# io.net
KiCad netlist of a schematic drawn in Altium Designer
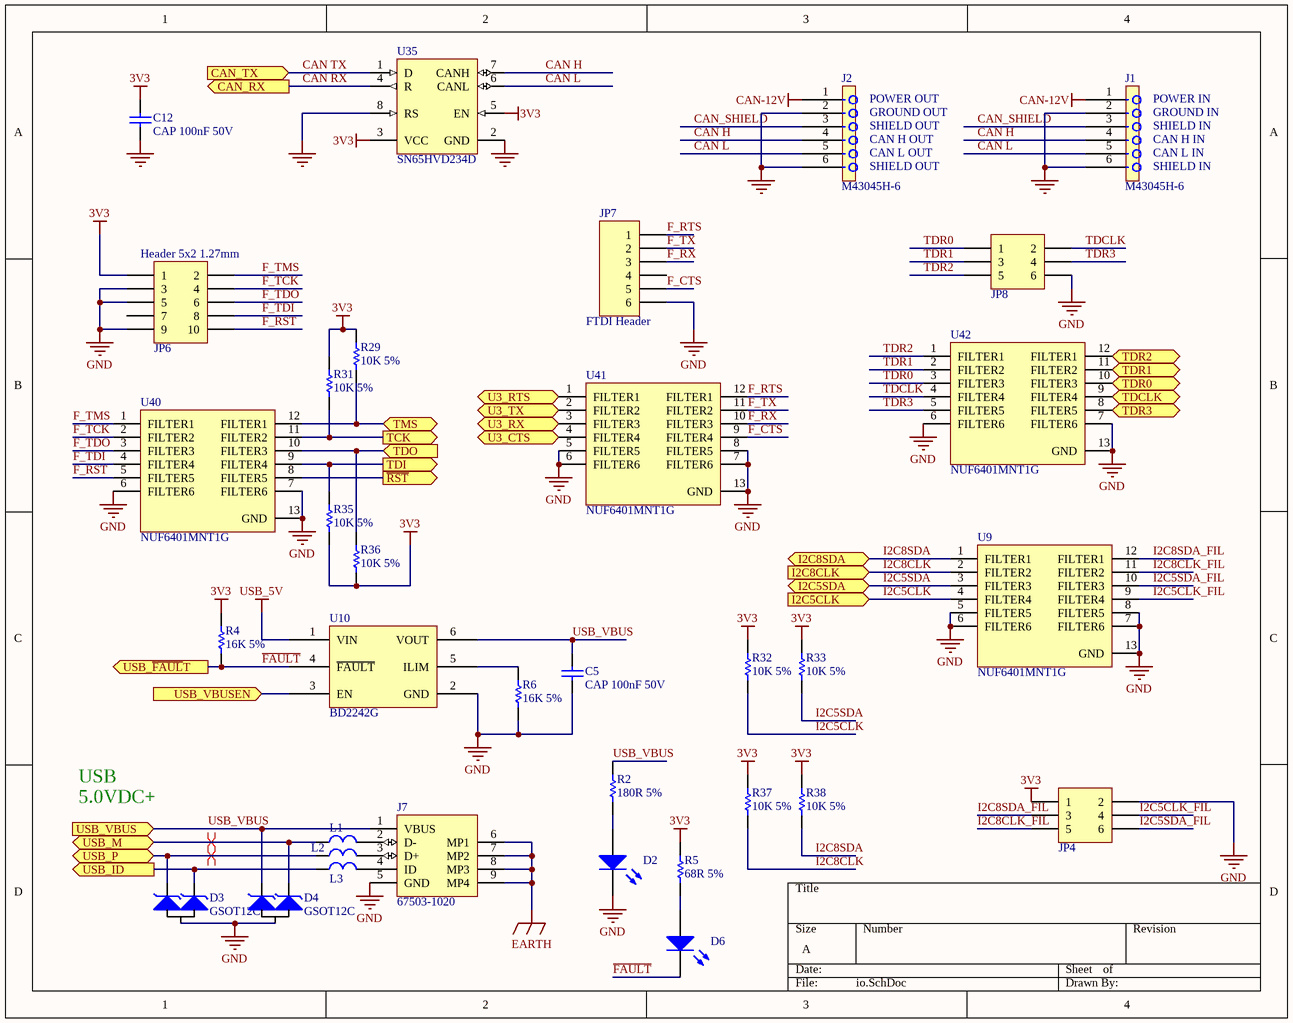
[diagram p0: io.SchDoc]

(export (version "E")
  (design (tool "Eeschema 10.0.6"))
  (components
    (comp (ref "C5")
      (value "CAP 100nF 50V")
      (footprint "CAPC0603(1608)100_M")
      (description "CAP 100nF 50V Â±0.1pF 0603 (1608 Metric) Thickness 1mm SMD")
      (fields (field (name "TOLERANCE") "Â±0.1pF"))
      (libsource (lib "Altium Content Vault") (part "CMP-1035-00010-1"))
    )
    (comp (ref "C12")
      (value "CAP 100nF 50V")
      (footprint "CAPC0603(1608)100_M")
      (description "CAP 100nF 50V Â±0.1pF 0603 (1608 Metric) Thickness 1mm SMD")
      (fields (field (name "TOLERANCE") "Â±0.1pF"))
      (libsource (lib "Altium Content Vault") (part "CMP-1035-00010-1"))
    )
    (comp (ref "D2")
      (value "LED")
      (footprint "LED-0603")
      (description "Typical RED, GREEN, YELLOW, AMBER GaAs LED")
      (fields (field (name "PUBLISHER") "Altium Limited"))
      (libsource (lib "HSBNE-Vend") (part "LED"))
    )
    (comp (ref "D3")
      (value "GSOT12C")
      (footprint "SOT-23 - ESD")
      (description "DIO GSOT12C ESD 2LINE 12V SOT23")
      (fields (field (name "MPN") "GSOT12C-E3-08"))
      (libsource (lib "HSBNE-Vend") (part "2749"))
    )
    (comp (ref "D4")
      (value "GSOT12C")
      (footprint "SOT-23 - ESD")
      (description "DIO GSOT12C ESD 2LINE 12V SOT23")
      (fields (field (name "MPN") "GSOT12C-E3-08"))
      (libsource (lib "HSBNE-Vend") (part "2749"))
    )
    (comp (ref "D6")
      (value "LED")
      (footprint "LED-0603")
      (description "Typical RED, GREEN, YELLOW, AMBER GaAs LED")
      (fields (field (name "PUBLISHER") "Altium Limited"))
      (libsource (lib "HSBNE-Vend") (part "LED"))
    )
    (comp (ref "J1") (value "M43045H-6") (footprint "M43045H-6") (libsource (lib "HSBNE-Vend") (part "CON6")))
    (comp (ref "J2") (value "M43045H-6") (footprint "M43045H-6") (libsource (lib "HSBNE-Vend") (part "CON6")))
    (comp (ref "J7")
      (value "67503-1020")
      (footprint "MOLX-67503-1020_V")
      (description "USB, MINI, SMD, RA KME04-USBMU03A01")
      (fields (field (name "MANUFACTURER") "Molex"))
      (libsource (lib "Altium Content Vault") (part "MOLX-67503-1020"))
    )
    (comp (ref "JP4")
      (value "Header 3x2 2.54mm")
      (footprint "2X3")
      (description "Header, 6-Pin")
      (libsource (lib "HSBNE-Vend") (part "Header 3x2"))
    )
    (comp (ref "JP6")
      (value "Header 5x2 1.27mm")
      (footprint "SOP10")
      (description "Program")
      (libsource (lib "HSBNE-Vend") (part "Header 5x2"))
    )
    (comp (ref "JP7")
      (value "FTDI Header")
      (footprint "1X6")
      (description "Header, 6-Pin")
      (libsource (lib "snarc+3") (part "Header 6"))
    )
    (comp (ref "JP8")
      (value "Header 3x2 2.54mm")
      (footprint "2X3")
      (description "Header, 6-Pin")
      (libsource (lib "HSBNE-Vend") (part "Header 3x2"))
    )
    (comp (ref "L1")
      (value "MPZ1608S102A")
      (footprint "0603")
      (description "IND FERRITE CHIP BEAD 1000 OHM @ 100MHz 800mA 0603")
      (libsource (lib "LXPN") (part "2982"))
    )
    (comp (ref "L2")
      (value "MPZ1608S102A")
      (footprint "0603")
      (description "IND FERRITE CHIP BEAD 1000 OHM @ 100MHz 800mA 0603")
      (libsource (lib "LXPN") (part "2982"))
    )
    (comp (ref "L3")
      (value "MPZ1608S102A")
      (footprint "0603")
      (description "IND FERRITE CHIP BEAD 1000 OHM @ 100MHz 800mA 0603")
      (libsource (lib "LXPN") (part "2982"))
    )
    (comp (ref "R2")
      (value "180R 5%")
      (footprint "RESC0603(1608)_L")
      (description "180R 0.1W 5% 0603 (1608 Metric)  SMD")
      (fields (field (name "POWER") "0.1 W") (field (name "TOLERANCE") "5 %"))
      (libsource (lib "Altium Content Vault") (part "CMP-1012-00056-1"))
    )
    (comp (ref "R4")
      (value "16K 5%")
      (footprint "RESC0603(1608)_L")
      (description "16K 0.1W 5% 0603 (1608 Metric)  SMD")
      (fields (field (name "TOLERANCE") "5 %") (field (name "POWER") "0.1 W"))
      (libsource (lib "Altium Content Vault") (part "RES"))
    )
    (comp (ref "R5")
      (value "68R 5%")
      (footprint "RESC0603(1608)_M")
      (description "68R 0.1W 5% 0603 (1608 Metric)  SMD")
      (fields (field (name "POWER") "0.1 W") (field (name "TOLERANCE") "5 %"))
      (libsource (lib "Altium Content Vault") (part "CMP-1012-00046-1"))
    )
    (comp (ref "R6")
      (value "16K 5%")
      (footprint "RESC0603(1608)_L")
      (description "16K 0.1W 5% 0603 (1608 Metric)  SMD")
      (fields (field (name "TOLERANCE") "5 %") (field (name "POWER") "0.1 W"))
      (libsource (lib "Altium Content Vault") (part "RES"))
    )
    (comp (ref "R29")
      (value "10K 5%")
      (footprint "RESC0603(1608)_N")
      (description "10K 0.1W 5% 0603 (1608 Metric)  SMD")
      (fields (field (name "TOLERANCE") "5 %") (field (name "POWER") "0.1 W"))
      (libsource (lib "Altium Content Vault") (part "RES"))
    )
    (comp (ref "R31")
      (value "10K 5%")
      (footprint "RESC0603(1608)_N")
      (description "10K 0.1W 5% 0603 (1608 Metric)  SMD")
      (fields (field (name "TOLERANCE") "5 %") (field (name "POWER") "0.1 W"))
      (libsource (lib "Altium Content Vault") (part "RES"))
    )
    (comp (ref "R32")
      (value "10K 5%")
      (footprint "RESC0603(1608)_N")
      (description "10K 0.1W 5% 0603 (1608 Metric)  SMD")
      (fields (field (name "TOLERANCE") "5 %") (field (name "POWER") "0.1 W"))
      (libsource (lib "Altium Content Vault") (part "RES"))
    )
    (comp (ref "R33")
      (value "10K 5%")
      (footprint "RESC0603(1608)_N")
      (description "10K 0.1W 5% 0603 (1608 Metric)  SMD")
      (fields (field (name "TOLERANCE") "5 %") (field (name "POWER") "0.1 W"))
      (libsource (lib "Altium Content Vault") (part "RES"))
    )
    (comp (ref "R35")
      (value "10K 5%")
      (footprint "RESC0603(1608)_N")
      (description "10K 0.1W 5% 0603 (1608 Metric)  SMD")
      (fields (field (name "TOLERANCE") "5 %") (field (name "POWER") "0.1 W"))
      (libsource (lib "Altium Content Vault") (part "RES"))
    )
    (comp (ref "R36")
      (value "10K 5%")
      (footprint "RESC0603(1608)_N")
      (description "10K 0.1W 5% 0603 (1608 Metric)  SMD")
      (fields (field (name "TOLERANCE") "5 %") (field (name "POWER") "0.1 W"))
      (libsource (lib "Altium Content Vault") (part "RES"))
    )
    (comp (ref "R37")
      (value "10K 5%")
      (footprint "RESC0603(1608)_N")
      (description "10K 0.1W 5% 0603 (1608 Metric)  SMD")
      (fields (field (name "TOLERANCE") "5 %") (field (name "POWER") "0.1 W"))
      (libsource (lib "Altium Content Vault") (part "RES"))
    )
    (comp (ref "R38")
      (value "10K 5%")
      (footprint "RESC0603(1608)_N")
      (description "10K 0.1W 5% 0603 (1608 Metric)  SMD")
      (fields (field (name "TOLERANCE") "5 %") (field (name "POWER") "0.1 W"))
      (libsource (lib "Altium Content Vault") (part "RES"))
    )
    (comp (ref "U9")
      (value "NUF6401MNT1G")
      (footprint "ONSC-DFN-12-506AD-01_V")
      (fields (field (name "MANUFACTURER") "On Semiconductor"))
      (libsource (lib "Altium Content Vault") (part "CMP-1066-00005-1"))
    )
    (comp (ref "U10")
      (value "BD2242G")
      (footprint "SOT23-6")
      (description "BD2242G-GTR")
      (libsource (lib "HSBNE-Vend") (part "RT9728A"))
    )
    (comp (ref "U35")
      (value "SN65HVD234D")
      (footprint "D8_M")
      (fields (field (name "MANUFACTURER") "Texas Instruments"))
      (libsource (lib "Altium Content Vault") (part "TI-SN65HVD234-SOIC_D-8"))
    )
    (comp (ref "U40")
      (value "NUF6401MNT1G")
      (footprint "ONSC-DFN-12-506AD-01_V")
      (fields (field (name "MANUFACTURER") "On Semiconductor"))
      (libsource (lib "HSBNE-Vend") (part "CMP-1066-00005-1"))
    )
    (comp (ref "U41")
      (value "NUF6401MNT1G")
      (footprint "ONSC-DFN-12-506AD-01_V")
      (fields (field (name "MANUFACTURER") "On Semiconductor"))
      (libsource (lib "HSBNE-Vend") (part "CMP-1066-00005-1"))
    )
    (comp (ref "U42")
      (value "NUF6401MNT1G")
      (footprint "ONSC-DFN-12-506AD-01_V")
      (fields (field (name "MANUFACTURER") "On Semiconductor"))
      (libsource (lib "HSBNE-Vend") (part "CMP-1066-00005-1"))
    )
  )
  (nets
    (net (code "1") (name "/CAN H") (class "Default")
      (node (ref "J1") (pin "4") (pintype "passive"))
      (node (ref "J2") (pin "4") (pintype "passive"))
      (node (ref "U35") (pin "7") (pinfunction "CANH_7") (pintype "bidirectional"))
    )
    (net (code "2") (name "/CAN L") (class "Default")
      (node (ref "J1") (pin "5") (pintype "passive"))
      (node (ref "J2") (pin "5") (pintype "passive"))
      (node (ref "U35") (pin "6") (pinfunction "CANL_6") (pintype "bidirectional"))
    )
    (net (code "3") (name "/CAN RX") (class "Default")
      (node (ref "U35") (pin "4") (pinfunction "R_4") (pintype "output"))
    )
    (net (code "4") (name "/CAN TX") (class "Default")
      (node (ref "U35") (pin "1") (pinfunction "D_1") (pintype "input"))
    )
    (net (code "5") (name "/CAN_SHIELD") (class "Default")
      (node (ref "J1") (pin "3") (pintype "passive"))
      (node (ref "J2") (pin "3") (pintype "passive"))
    )
    (net (code "6") (name "/F_CTS") (class "Default")
      (node (ref "JP7") (pin "5") (pinfunction "5_5") (pintype "passive"))
      (node (ref "U41") (pin "9") (pinfunction "FILTER4_9") (pintype "passive"))
    )
    (net (code "7") (name "/F_RTS") (class "Default")
      (node (ref "JP7") (pin "1") (pinfunction "1_1") (pintype "passive"))
      (node (ref "U41") (pin "12") (pinfunction "FILTER1_12") (pintype "passive"))
    )
    (net (code "8") (name "/F_RX") (class "Default")
      (node (ref "JP7") (pin "3") (pinfunction "3_3") (pintype "passive"))
      (node (ref "U41") (pin "10") (pinfunction "FILTER3_10") (pintype "passive"))
    )
    (net (code "9") (name "/F_TCK") (class "Default")
      (node (ref "JP6") (pin "4") (pinfunction "4_4") (pintype "passive"))
      (node (ref "U40") (pin "2") (pinfunction "FILTER2_2") (pintype "passive"))
    )
    (net (code "10") (name "/F_TDI") (class "Default")
      (node (ref "JP6") (pin "8") (pinfunction "8_8") (pintype "passive"))
      (node (ref "U40") (pin "4") (pinfunction "FILTER4_4") (pintype "passive"))
    )
    (net (code "11") (name "/F_TDO") (class "Default")
      (node (ref "JP6") (pin "6") (pinfunction "6_6") (pintype "passive"))
      (node (ref "U40") (pin "3") (pinfunction "FILTER3_3") (pintype "passive"))
    )
    (net (code "12") (name "/F_TMS") (class "Default")
      (node (ref "JP6") (pin "2") (pinfunction "2_2") (pintype "passive"))
      (node (ref "U40") (pin "1") (pinfunction "FILTER1_1") (pintype "passive"))
    )
    (net (code "13") (name "/F_TX") (class "Default")
      (node (ref "JP7") (pin "2") (pinfunction "2_2") (pintype "passive"))
      (node (ref "U41") (pin "11") (pinfunction "FILTER2_11") (pintype "passive"))
    )
    (net (code "14") (name "/F_~{RST}") (class "Default")
      (node (ref "JP6") (pin "10") (pinfunction "10_10") (pintype "passive"))
      (node (ref "U40") (pin "5") (pinfunction "FILTER5_5") (pintype "passive"))
    )
    (net (code "15") (name "/I2C5CLK") (class "Default")
      (node (ref "R32") (pin "1") (pinfunction "1_1") (pintype "passive"))
      (node (ref "U9") (pin "4") (pinfunction "FILTER4_4") (pintype "passive"))
    )
    (net (code "16") (name "/I2C5CLK_FIL") (class "Default")
      (node (ref "JP4") (pin "4") (pinfunction "4_4") (pintype "passive"))
      (node (ref "U9") (pin "9") (pinfunction "FILTER4_9") (pintype "passive"))
    )
    (net (code "17") (name "/I2C5SDA") (class "Default")
      (node (ref "R33") (pin "1") (pinfunction "1_1") (pintype "passive"))
      (node (ref "U9") (pin "3") (pinfunction "FILTER3_3") (pintype "passive"))
    )
    (net (code "18") (name "/I2C5SDA_FIL") (class "Default")
      (node (ref "JP4") (pin "6") (pinfunction "6_6") (pintype "passive"))
      (node (ref "U9") (pin "10") (pinfunction "FILTER3_10") (pintype "passive"))
    )
    (net (code "19") (name "/I2C8CLK") (class "Default")
      (node (ref "R37") (pin "1") (pinfunction "1_1") (pintype "passive"))
      (node (ref "U9") (pin "2") (pinfunction "FILTER2_2") (pintype "passive"))
    )
    (net (code "20") (name "/I2C8CLK_FIL") (class "Default")
      (node (ref "JP4") (pin "5") (pinfunction "5_5") (pintype "passive"))
      (node (ref "U9") (pin "11") (pinfunction "FILTER2_11") (pintype "passive"))
    )
    (net (code "21") (name "/I2C8SDA") (class "Default")
      (node (ref "R38") (pin "1") (pinfunction "1_1") (pintype "passive"))
      (node (ref "U9") (pin "1") (pinfunction "FILTER1_1") (pintype "passive"))
    )
    (net (code "22") (name "/I2C8SDA_FIL") (class "Default")
      (node (ref "JP4") (pin "3") (pinfunction "3_3") (pintype "passive"))
      (node (ref "U9") (pin "12") (pinfunction "FILTER1_12") (pintype "passive"))
    )
    (net (code "23") (name "/TCK") (class "Default")
      (node (ref "R31") (pin "1") (pinfunction "1_1") (pintype "passive"))
      (node (ref "U40") (pin "11") (pinfunction "FILTER2_11") (pintype "passive"))
    )
    (net (code "24") (name "/TDCLK") (class "Default")
      (node (ref "JP8") (pin "2") (pinfunction "2_2") (pintype "passive"))
      (node (ref "U42") (pin "4") (pinfunction "FILTER4_4") (pintype "passive"))
    )
    (net (code "25") (name "/TDI") (class "Default")
      (node (ref "R35") (pin "2") (pinfunction "2_2") (pintype "passive"))
      (node (ref "U40") (pin "9") (pinfunction "FILTER4_9") (pintype "passive"))
    )
    (net (code "26") (name "/TDO") (class "Default")
      (node (ref "R36") (pin "2") (pinfunction "2_2") (pintype "passive"))
      (node (ref "U40") (pin "10") (pinfunction "FILTER3_10") (pintype "passive"))
    )
    (net (code "27") (name "/TDR0") (class "Default")
      (node (ref "JP8") (pin "1") (pinfunction "1_1") (pintype "passive"))
      (node (ref "U42") (pin "3") (pinfunction "FILTER3_3") (pintype "passive"))
    )
    (net (code "28") (name "/TDR1") (class "Default")
      (node (ref "JP8") (pin "3") (pinfunction "3_3") (pintype "passive"))
      (node (ref "U42") (pin "2") (pinfunction "FILTER2_2") (pintype "passive"))
    )
    (net (code "29") (name "/TDR2") (class "Default")
      (node (ref "JP8") (pin "5") (pinfunction "5_5") (pintype "passive"))
      (node (ref "U42") (pin "1") (pinfunction "FILTER1_1") (pintype "passive"))
    )
    (net (code "30") (name "/TDR3") (class "Default")
      (node (ref "JP8") (pin "4") (pinfunction "4_4") (pintype "passive"))
      (node (ref "U42") (pin "5") (pinfunction "FILTER5_5") (pintype "passive"))
    )
    (net (code "31") (name "/TMS") (class "Default")
      (node (ref "R29") (pin "1") (pinfunction "1_1") (pintype "passive"))
      (node (ref "U40") (pin "12") (pinfunction "FILTER1_12") (pintype "passive"))
    )
    (net (code "32") (name "/U3_CTS") (class "Default")
      (node (ref "U41") (pin "4") (pinfunction "FILTER4_4") (pintype "passive"))
    )
    (net (code "33") (name "/U3_RTS") (class "Default")
      (node (ref "U41") (pin "1") (pinfunction "FILTER1_1") (pintype "passive"))
    )
    (net (code "34") (name "/U3_RX") (class "Default")
      (node (ref "U41") (pin "3") (pinfunction "FILTER3_3") (pintype "passive"))
    )
    (net (code "35") (name "/U3_TX") (class "Default")
      (node (ref "U41") (pin "2") (pinfunction "FILTER2_2") (pintype "passive"))
    )
    (net (code "36") (name "/USB_ID") (class "Default")
      (node (ref "D3") (pin "2") (pinfunction "K2_2") (pintype "passive"))
      (node (ref "L3") (pin "1") (pinfunction "1_1") (pintype "passive"))
    )
    (net (code "37") (name "/USB_M") (class "Default")
      (node (ref "D4") (pin "2") (pinfunction "K2_2") (pintype "passive"))
      (node (ref "L1") (pin "1") (pinfunction "1_1") (pintype "passive"))
    )
    (net (code "38") (name "/USB_P") (class "Default")
      (node (ref "D3") (pin "1") (pinfunction "K1_1") (pintype "passive"))
      (node (ref "L2") (pin "1") (pinfunction "1_1") (pintype "passive"))
    )
    (net (code "39") (name "/USB_VBUS") (class "Default")
      (node (ref "C5") (pin "2") (pinfunction "2_2") (pintype "passive"))
      (node (ref "D4") (pin "1") (pinfunction "K1_1") (pintype "passive"))
      (node (ref "J7") (pin "1") (pinfunction "VBUS_1") (pintype "power_in"))
      (node (ref "R2") (pin "2") (pinfunction "2_2") (pintype "passive"))
      (node (ref "U10") (pin "6") (pinfunction "VOUT_6") (pintype "passive"))
    )
    (net (code "40") (name "/USB_VBUSEN") (class "Default")
      (node (ref "U10") (pin "3") (pinfunction "EN_3") (pintype "passive"))
    )
    (net (code "41") (name "/~{FAULT}") (class "Default")
      (node (ref "D6") (pin "2") (pinfunction "K_2") (pintype "passive"))
      (node (ref "R4") (pin "1") (pinfunction "1_1") (pintype "passive"))
      (node (ref "U10") (pin "4") (pinfunction "~{FAULT}_4") (pintype "passive"))
    )
    (net (code "42") (name "/~{RST}") (class "Default")
      (node (ref "U40") (pin "8") (pinfunction "FILTER5_8") (pintype "passive"))
    )
    (net (code "43") (name "3V3") (class "Default")
      (node (ref "C12") (pin "2") (pinfunction "2_2") (pintype "passive"))
      (node (ref "JP4") (pin "1") (pinfunction "1_1") (pintype "passive"))
      (node (ref "JP6") (pin "1") (pinfunction "1_1") (pintype "passive"))
      (node (ref "R29") (pin "2") (pinfunction "2_2") (pintype "passive"))
      (node (ref "R31") (pin "2") (pinfunction "2_2") (pintype "passive"))
      (node (ref "R32") (pin "2") (pinfunction "2_2") (pintype "passive"))
      (node (ref "R33") (pin "2") (pinfunction "2_2") (pintype "passive"))
      (node (ref "R35") (pin "1") (pinfunction "1_1") (pintype "passive"))
      (node (ref "R36") (pin "1") (pinfunction "1_1") (pintype "passive"))
      (node (ref "R37") (pin "2") (pinfunction "2_2") (pintype "passive"))
      (node (ref "R38") (pin "2") (pinfunction "2_2") (pintype "passive"))
      (node (ref "R4") (pin "2") (pinfunction "2_2") (pintype "passive"))
      (node (ref "R5") (pin "2") (pinfunction "2_2") (pintype "passive"))
      (node (ref "U35") (pin "3") (pinfunction "VCC_3") (pintype "power_in"))
      (node (ref "U35") (pin "5") (pinfunction "EN_5") (pintype "input"))
    )
    (net (code "44") (name "CAN-12V") (class "Default")
      (node (ref "J1") (pin "1") (pintype "passive"))
      (node (ref "J2") (pin "1") (pintype "passive"))
    )
    (net (code "45") (name "EARTH") (class "Default")
      (node (ref "J7") (pin "6") (pinfunction "MP1_6") (pintype "passive"))
      (node (ref "J7") (pin "7") (pinfunction "MP2_7") (pintype "passive"))
      (node (ref "J7") (pin "8") (pinfunction "MP3_8") (pintype "passive"))
      (node (ref "J7") (pin "9") (pinfunction "MP4_9") (pintype "passive"))
    )
    (net (code "46") (name "GND") (class "Default")
      (node (ref "C12") (pin "1") (pinfunction "1_1") (pintype "passive"))
      (node (ref "C5") (pin "1") (pinfunction "1_1") (pintype "passive"))
      (node (ref "D2") (pin "2") (pinfunction "K_2") (pintype "passive"))
      (node (ref "D3") (pin "3") (pinfunction "A_3") (pintype "passive"))
      (node (ref "D4") (pin "3") (pinfunction "A_3") (pintype "passive"))
      (node (ref "J1") (pin "2") (pintype "passive"))
      (node (ref "J1") (pin "6") (pintype "passive"))
      (node (ref "J2") (pin "2") (pintype "passive"))
      (node (ref "J2") (pin "6") (pintype "passive"))
      (node (ref "J7") (pin "5") (pinfunction "GND_5") (pintype "power_in"))
      (node (ref "JP4") (pin "2") (pinfunction "2_2") (pintype "passive"))
      (node (ref "JP6") (pin "3") (pinfunction "3_3") (pintype "passive"))
      (node (ref "JP6") (pin "5") (pinfunction "5_5") (pintype "passive"))
      (node (ref "JP6") (pin "9") (pinfunction "9_9") (pintype "passive"))
      (node (ref "JP7") (pin "6") (pinfunction "6_6") (pintype "passive"))
      (node (ref "JP8") (pin "6") (pinfunction "6_6") (pintype "passive"))
      (node (ref "R6") (pin "1") (pinfunction "1_1") (pintype "passive"))
      (node (ref "U10") (pin "2") (pinfunction "GND_2") (pintype "passive"))
      (node (ref "U35") (pin "2") (pinfunction "GND_2") (pintype "power_in"))
      (node (ref "U35") (pin "8") (pinfunction "RS_8") (pintype "input"))
      (node (ref "U40") (pin "13") (pinfunction "GND_13") (pintype "power_in"))
      (node (ref "U40") (pin "6") (pinfunction "FILTER6_6") (pintype "passive"))
      (node (ref "U40") (pin "7") (pinfunction "FILTER6_7") (pintype "passive"))
      (node (ref "U41") (pin "13") (pinfunction "GND_13") (pintype "power_in"))
      (node (ref "U41") (pin "5") (pinfunction "FILTER5_5") (pintype "passive"))
      (node (ref "U41") (pin "6") (pinfunction "FILTER6_6") (pintype "passive"))
      (node (ref "U41") (pin "7") (pinfunction "FILTER6_7") (pintype "passive"))
      (node (ref "U41") (pin "8") (pinfunction "FILTER5_8") (pintype "passive"))
      (node (ref "U42") (pin "13") (pinfunction "GND_13") (pintype "power_in"))
      (node (ref "U42") (pin "6") (pinfunction "FILTER6_6") (pintype "passive"))
      (node (ref "U42") (pin "7") (pinfunction "FILTER6_7") (pintype "passive"))
      (node (ref "U9") (pin "13") (pinfunction "GND_13") (pintype "power_in"))
      (node (ref "U9") (pin "5") (pinfunction "FILTER5_5") (pintype "passive"))
      (node (ref "U9") (pin "6") (pinfunction "FILTER6_6") (pintype "passive"))
      (node (ref "U9") (pin "7") (pinfunction "FILTER6_7") (pintype "passive"))
      (node (ref "U9") (pin "8") (pinfunction "FILTER5_8") (pintype "passive"))
    )
    (net (code "47") (name "Net-(D2-A)") (class "Default")
      (node (ref "D2") (pin "1") (pinfunction "A_1") (pintype "passive"))
      (node (ref "R2") (pin "1") (pinfunction "1_1") (pintype "passive"))
    )
    (net (code "48") (name "Net-(D6-A)") (class "Default")
      (node (ref "D6") (pin "1") (pinfunction "A_1") (pintype "passive"))
      (node (ref "R5") (pin "1") (pinfunction "1_1") (pintype "passive"))
    )
    (net (code "49") (name "Net-(J7-D+)") (class "Default")
      (node (ref "J7") (pin "3") (pinfunction "D+_3") (pintype "bidirectional"))
      (node (ref "L2") (pin "2") (pinfunction "2_2") (pintype "passive"))
    )
    (net (code "50") (name "Net-(J7-D-)") (class "Default")
      (node (ref "J7") (pin "2") (pinfunction "D-_2") (pintype "bidirectional"))
      (node (ref "L1") (pin "2") (pinfunction "2_2") (pintype "passive"))
    )
    (net (code "51") (name "Net-(J7-ID)") (class "Default")
      (node (ref "J7") (pin "4") (pinfunction "ID_4") (pintype "passive"))
      (node (ref "L3") (pin "2") (pinfunction "2_2") (pintype "passive"))
    )
    (net (code "52") (name "Net-(U10-ILIM)") (class "Default")
      (node (ref "R6") (pin "2") (pinfunction "2_2") (pintype "passive"))
      (node (ref "U10") (pin "5") (pinfunction "ILIM_5") (pintype "passive"))
    )
    (net (code "53") (name "USB_5V") (class "Default")
      (node (ref "U10") (pin "1") (pinfunction "VIN_1") (pintype "passive"))
    )
    (net (code "54") (name "unconnected-(JP6-Pad7)") (class "Default")
      (node (ref "JP6") (pin "7") (pinfunction "7_7") (pintype "passive"))
    )
    (net (code "55") (name "unconnected-(JP7-Pad4)") (class "Default")
      (node (ref "JP7") (pin "4") (pinfunction "4_4") (pintype "passive"))
    )
    (net (code "56") (name "unconnected-(U42-FILTER1-Pad12)") (class "Default")
      (node (ref "U42") (pin "12") (pinfunction "FILTER1_12") (pintype "passive"))
    )
    (net (code "57") (name "unconnected-(U42-FILTER2-Pad11)") (class "Default")
      (node (ref "U42") (pin "11") (pinfunction "FILTER2_11") (pintype "passive"))
    )
    (net (code "58") (name "unconnected-(U42-FILTER3-Pad10)") (class "Default")
      (node (ref "U42") (pin "10") (pinfunction "FILTER3_10") (pintype "passive"))
    )
    (net (code "59") (name "unconnected-(U42-FILTER4-Pad9)") (class "Default")
      (node (ref "U42") (pin "9") (pinfunction "FILTER4_9") (pintype "passive"))
    )
    (net (code "60") (name "unconnected-(U42-FILTER5-Pad8)") (class "Default")
      (node (ref "U42") (pin "8") (pinfunction "FILTER5_8") (pintype "passive"))
    )
  )
)
